# STM32F7.net
KiCad netlist of a schematic drawn in Altium Designer
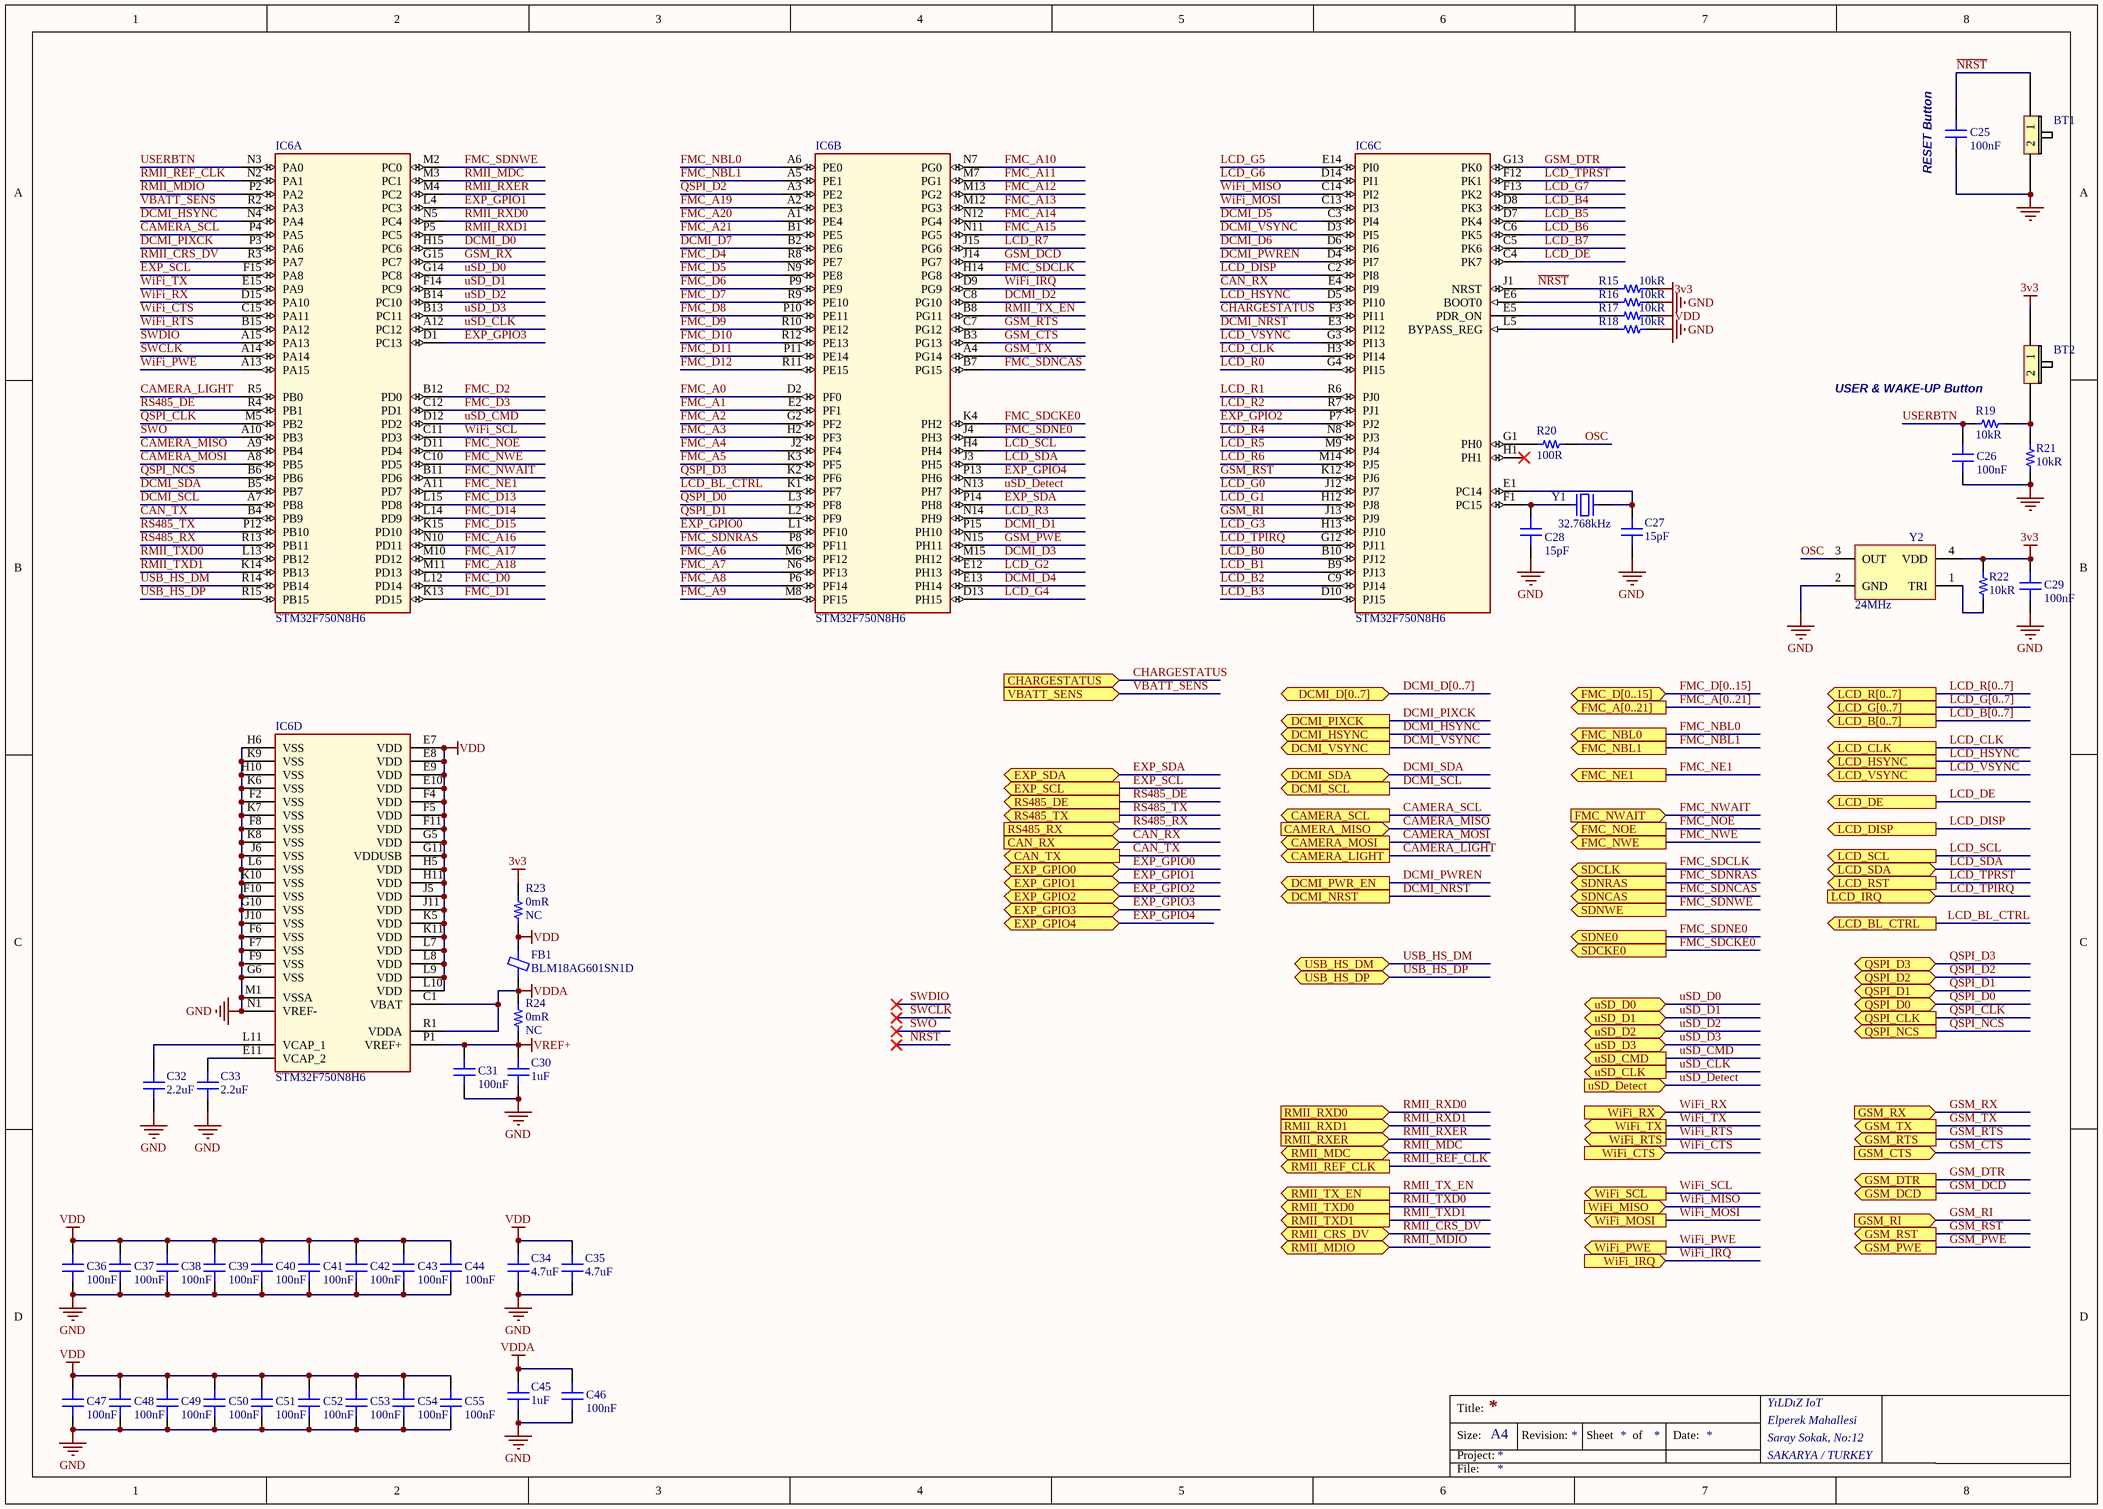
[diagram p0: STM32F7.SchDoc]

(export (version "E")
  (design (tool "Eeschema 10.0.6"))
  (components
    (comp (ref "BT1")
      (value "EVQP7J01P")
      (footprint "TactileButton")
      (description "Button, 2 pin")
      (fields (field (name "MANUFACTURER") "Panasonic"))
      (libsource (lib "Muhammet_All_In_One") (part "Button"))
    )
    (comp (ref "BT2")
      (value "EVQP7J01P")
      (footprint "TactileButton")
      (description "Button, 2 pin")
      (fields (field (name "MANUFACTURER") "Panasonic"))
      (libsource (lib "Muhammet_All_In_One") (part "Button"))
    )
    (comp (ref "C25")
      (value "100nF")
      (footprint "CAP 0603/1608")
      (description "Ceramic, SMT Capacitor")
      (fields
        (field (name "MANUFACTURER") "Samsung")
        (field (name "MANUFACTURER PART NUMBER") "CL10B104JB8NNNC")
      )
      (libsource (lib "yildizIoT Library") (part "Capacitor - Ceramic"))
    )
    (comp (ref "C26")
      (value "100nF")
      (footprint "CAP 0603/1608")
      (description "Ceramic, SMT Capacitor")
      (fields
        (field (name "MANUFACTURER") "Samsung")
        (field (name "MANUFACTURER PART NUMBER") "CL10B104JB8NNNC")
      )
      (libsource (lib "yildizIoT Library") (part "Capacitor - Ceramic"))
    )
    (comp (ref "C27")
      (value "15pF")
      (footprint "CAP 0603/1608")
      (description "Ceramic, SMT Capacitor")
      (fields
        (field (name "MANUFACTURER") "Walsin Technologies")
        (field (name "MANUFACTURER PART NUMBER") "0603N150J500CT")
      )
      (libsource (lib "yildizIoT Library") (part "Capacitor - Ceramic"))
    )
    (comp (ref "C28")
      (value "15pF")
      (footprint "CAP 0603/1608")
      (description "Ceramic, SMT Capacitor")
      (fields
        (field (name "MANUFACTURER") "Walsin Technologies")
        (field (name "MANUFACTURER PART NUMBER") "0603N150J500CT")
      )
      (libsource (lib "yildizIoT Library") (part "Capacitor - Ceramic"))
    )
    (comp (ref "C29")
      (value "100nF")
      (footprint "CAP 0603/1608")
      (description "Ceramic, SMT Capacitor")
      (fields
        (field (name "MANUFACTURER") "Samsung")
        (field (name "MANUFACTURER PART NUMBER") "CL10B104JB8NNNC")
      )
      (libsource (lib "yildizIoT Library") (part "Capacitor - Ceramic"))
    )
    (comp (ref "C30")
      (value "1uF")
      (footprint "CAP 0603/1608")
      (description "Ceramic, SMT Capacitor")
      (fields
        (field (name "MANUFACTURER") "Samsung")
        (field (name "MANUFACTURER PART NUMBER") "CL10A105KP8NNNC")
      )
      (libsource (lib "yildizIoT Library") (part "Capacitor - Ceramic"))
    )
    (comp (ref "C31")
      (value "100nF")
      (footprint "CAP 0603/1608")
      (description "Ceramic, SMT Capacitor")
      (fields
        (field (name "MANUFACTURER") "Samsung")
        (field (name "MANUFACTURER PART NUMBER") "CL10B104JB8NNNC")
      )
      (libsource (lib "yildizIoT Library") (part "Capacitor - Ceramic"))
    )
    (comp (ref "C32")
      (value "2.2uF")
      (footprint "CAP 0603/1608")
      (description "Ceramic, SMT Capacitor")
      (fields
        (field (name "MANUFACTURER") "Samsung")
        (field (name "MANUFACTURER PART NUMBER") "CL10A225KQ8NNNC")
      )
      (libsource (lib "yildizIoT Library") (part "Capacitor - Ceramic"))
    )
    (comp (ref "C33")
      (value "2.2uF")
      (footprint "CAP 0603/1608")
      (description "Ceramic, SMT Capacitor")
      (fields
        (field (name "MANUFACTURER") "Samsung")
        (field (name "MANUFACTURER PART NUMBER") "CL10A225KQ8NNNC")
      )
      (libsource (lib "yildizIoT Library") (part "Capacitor - Ceramic"))
    )
    (comp (ref "C34")
      (value "4.7uF")
      (footprint "CAP 0603/1608")
      (description "Ceramic, SMT Capacitor")
      (fields
        (field (name "MANUFACTURER") "Samsung")
        (field (name "MANUFACTURER PART NUMBER") "CL10A475MQ8NNNC")
      )
      (libsource (lib "yildizIoT Library") (part "Capacitor - Ceramic"))
    )
    (comp (ref "C35")
      (value "4.7uF")
      (footprint "CAP 0603/1608")
      (description "Ceramic, SMT Capacitor")
      (fields
        (field (name "MANUFACTURER") "Samsung")
        (field (name "MANUFACTURER PART NUMBER") "CL10A475MQ8NNNC")
      )
      (libsource (lib "yildizIoT Library") (part "Capacitor - Ceramic"))
    )
    (comp (ref "C36")
      (value "100nF")
      (footprint "CAP 0603/1608")
      (description "Ceramic, SMT Capacitor")
      (fields
        (field (name "MANUFACTURER") "Samsung")
        (field (name "MANUFACTURER PART NUMBER") "CL10B104JB8NNNC")
      )
      (libsource (lib "yildizIoT Library") (part "Capacitor - Ceramic"))
    )
    (comp (ref "C37")
      (value "100nF")
      (footprint "CAP 0603/1608")
      (description "Ceramic, SMT Capacitor")
      (fields
        (field (name "MANUFACTURER") "Samsung")
        (field (name "MANUFACTURER PART NUMBER") "CL10B104JB8NNNC")
      )
      (libsource (lib "yildizIoT Library") (part "Capacitor - Ceramic"))
    )
    (comp (ref "C38")
      (value "100nF")
      (footprint "CAP 0603/1608")
      (description "Ceramic, SMT Capacitor")
      (fields
        (field (name "MANUFACTURER") "Samsung")
        (field (name "MANUFACTURER PART NUMBER") "CL10B104JB8NNNC")
      )
      (libsource (lib "yildizIoT Library") (part "Capacitor - Ceramic"))
    )
    (comp (ref "C39")
      (value "100nF")
      (footprint "CAP 0603/1608")
      (description "Ceramic, SMT Capacitor")
      (fields
        (field (name "MANUFACTURER") "Samsung")
        (field (name "MANUFACTURER PART NUMBER") "CL10B104JB8NNNC")
      )
      (libsource (lib "yildizIoT Library") (part "Capacitor - Ceramic"))
    )
    (comp (ref "C40")
      (value "100nF")
      (footprint "CAP 0603/1608")
      (description "Ceramic, SMT Capacitor")
      (fields
        (field (name "MANUFACTURER") "Samsung")
        (field (name "MANUFACTURER PART NUMBER") "CL10B104JB8NNNC")
      )
      (libsource (lib "yildizIoT Library") (part "Capacitor - Ceramic"))
    )
    (comp (ref "C41")
      (value "100nF")
      (footprint "CAP 0603/1608")
      (description "Ceramic, SMT Capacitor")
      (fields
        (field (name "MANUFACTURER") "Samsung")
        (field (name "MANUFACTURER PART NUMBER") "CL10B104JB8NNNC")
      )
      (libsource (lib "yildizIoT Library") (part "Capacitor - Ceramic"))
    )
    (comp (ref "C42")
      (value "100nF")
      (footprint "CAP 0603/1608")
      (description "Ceramic, SMT Capacitor")
      (fields
        (field (name "MANUFACTURER") "Samsung")
        (field (name "MANUFACTURER PART NUMBER") "CL10B104JB8NNNC")
      )
      (libsource (lib "yildizIoT Library") (part "Capacitor - Ceramic"))
    )
    (comp (ref "C43")
      (value "100nF")
      (footprint "CAP 0603/1608")
      (description "Ceramic, SMT Capacitor")
      (fields
        (field (name "MANUFACTURER") "Samsung")
        (field (name "MANUFACTURER PART NUMBER") "CL10B104JB8NNNC")
      )
      (libsource (lib "yildizIoT Library") (part "Capacitor - Ceramic"))
    )
    (comp (ref "C44")
      (value "100nF")
      (footprint "CAP 0603/1608")
      (description "Ceramic, SMT Capacitor")
      (fields
        (field (name "MANUFACTURER") "Samsung")
        (field (name "MANUFACTURER PART NUMBER") "CL10B104JB8NNNC")
      )
      (libsource (lib "yildizIoT Library") (part "Capacitor - Ceramic"))
    )
    (comp (ref "C45")
      (value "1uF")
      (footprint "CAP 0603/1608")
      (description "Ceramic, SMT Capacitor")
      (fields
        (field (name "MANUFACTURER") "Samsung")
        (field (name "MANUFACTURER PART NUMBER") "CL10A105KP8NNNC")
      )
      (libsource (lib "yildizIoT Library") (part "Capacitor - Ceramic"))
    )
    (comp (ref "C46")
      (value "100nF")
      (footprint "CAP 0603/1608")
      (description "Ceramic, SMT Capacitor")
      (fields
        (field (name "MANUFACTURER") "Samsung")
        (field (name "MANUFACTURER PART NUMBER") "CL10B104JB8NNNC")
      )
      (libsource (lib "yildizIoT Library") (part "Capacitor - Ceramic"))
    )
    (comp (ref "C47")
      (value "100nF")
      (footprint "CAP 0603/1608")
      (description "Ceramic, SMT Capacitor")
      (fields
        (field (name "MANUFACTURER") "Samsung")
        (field (name "MANUFACTURER PART NUMBER") "CL10B104JB8NNNC")
      )
      (libsource (lib "yildizIoT Library") (part "Capacitor - Ceramic"))
    )
    (comp (ref "C48")
      (value "100nF")
      (footprint "CAP 0603/1608")
      (description "Ceramic, SMT Capacitor")
      (fields
        (field (name "MANUFACTURER") "Samsung")
        (field (name "MANUFACTURER PART NUMBER") "CL10B104JB8NNNC")
      )
      (libsource (lib "yildizIoT Library") (part "Capacitor - Ceramic"))
    )
    (comp (ref "C49")
      (value "100nF")
      (footprint "CAP 0603/1608")
      (description "Ceramic, SMT Capacitor")
      (fields
        (field (name "MANUFACTURER") "Samsung")
        (field (name "MANUFACTURER PART NUMBER") "CL10B104JB8NNNC")
      )
      (libsource (lib "yildizIoT Library") (part "Capacitor - Ceramic"))
    )
    (comp (ref "C50")
      (value "100nF")
      (footprint "CAP 0603/1608")
      (description "Ceramic, SMT Capacitor")
      (fields
        (field (name "MANUFACTURER") "Samsung")
        (field (name "MANUFACTURER PART NUMBER") "CL10B104JB8NNNC")
      )
      (libsource (lib "yildizIoT Library") (part "Capacitor - Ceramic"))
    )
    (comp (ref "C51")
      (value "100nF")
      (footprint "CAP 0603/1608")
      (description "Ceramic, SMT Capacitor")
      (fields
        (field (name "MANUFACTURER") "Samsung")
        (field (name "MANUFACTURER PART NUMBER") "CL10B104JB8NNNC")
      )
      (libsource (lib "yildizIoT Library") (part "Capacitor - Ceramic"))
    )
    (comp (ref "C52")
      (value "100nF")
      (footprint "CAP 0603/1608")
      (description "Ceramic, SMT Capacitor")
      (fields
        (field (name "MANUFACTURER") "Samsung")
        (field (name "MANUFACTURER PART NUMBER") "CL10B104JB8NNNC")
      )
      (libsource (lib "yildizIoT Library") (part "Capacitor - Ceramic"))
    )
    (comp (ref "C53")
      (value "100nF")
      (footprint "CAP 0603/1608")
      (description "Ceramic, SMT Capacitor")
      (fields
        (field (name "MANUFACTURER") "Samsung")
        (field (name "MANUFACTURER PART NUMBER") "CL10B104JB8NNNC")
      )
      (libsource (lib "yildizIoT Library") (part "Capacitor - Ceramic"))
    )
    (comp (ref "C54")
      (value "100nF")
      (footprint "CAP 0603/1608")
      (description "Ceramic, SMT Capacitor")
      (fields
        (field (name "MANUFACTURER") "Samsung")
        (field (name "MANUFACTURER PART NUMBER") "CL10B104JB8NNNC")
      )
      (libsource (lib "yildizIoT Library") (part "Capacitor - Ceramic"))
    )
    (comp (ref "C55")
      (value "100nF")
      (footprint "CAP 0603/1608")
      (description "Ceramic, SMT Capacitor")
      (fields
        (field (name "MANUFACTURER") "Samsung")
        (field (name "MANUFACTURER PART NUMBER") "CL10B104JB8NNNC")
      )
      (libsource (lib "yildizIoT Library") (part "Capacitor - Ceramic"))
    )
    (comp (ref "FB1")
      (value "BLM18AG601SN1D")
      (footprint "FER 0603/1608")
      (description "SMT Ferrite Chip")
      (fields (field (name "MANUFACTURER") "Murata") (field (name "TOLERANCE") "25%"))
      (libsource (lib "yildizIoT Library") (part "Ferrite Chip"))
    )
    (comp (ref "IC6")
      (value "STM32F750N8H6")
      (footprint "ST TFBGA-216 13x13 0.8mm")
      (fields (field (name "MANUFACTURER") "STMicroelectronics"))
      (libsource (lib "") (part "ST STM32F75XNXH 216 PIN_2"))
    )
    (comp (ref "R15")
      (value "10kR")
      (footprint "RES 0603/1608")
      (description "Ceramic, SMT Capacitor")
      (fields
        (field (name "MANUFACTURER") "Stackpole Electronics")
        (field (name "MANUFACTURER PART NUMBER") "RNCP0603FTD10K0")
      )
      (libsource (lib "yildizIoT Library") (part "Resistor_Chip"))
    )
    (comp (ref "R16")
      (value "10kR")
      (footprint "RES 0603/1608")
      (description "Ceramic, SMT Capacitor")
      (fields
        (field (name "MANUFACTURER") "Stackpole Electronics")
        (field (name "MANUFACTURER PART NUMBER") "RNCP0603FTD10K0")
      )
      (libsource (lib "yildizIoT Library") (part "Resistor_Chip"))
    )
    (comp (ref "R17")
      (value "10kR")
      (footprint "RES 0603/1608")
      (description "Ceramic, SMT Capacitor")
      (fields
        (field (name "MANUFACTURER") "Stackpole Electronics")
        (field (name "MANUFACTURER PART NUMBER") "RNCP0603FTD10K0")
      )
      (libsource (lib "yildizIoT Library") (part "Resistor_Chip"))
    )
    (comp (ref "R18")
      (value "10kR")
      (footprint "RES 0603/1608")
      (description "Ceramic, SMT Capacitor")
      (fields
        (field (name "MANUFACTURER") "Stackpole Electronics")
        (field (name "MANUFACTURER PART NUMBER") "RNCP0603FTD10K0")
      )
      (libsource (lib "yildizIoT Library") (part "Resistor_Chip"))
    )
    (comp (ref "R19")
      (value "10kR")
      (footprint "RES 0603/1608")
      (description "Ceramic, SMT Capacitor")
      (fields
        (field (name "MANUFACTURER") "Stackpole Electronics")
        (field (name "MANUFACTURER PART NUMBER") "RNCP0603FTD10K0")
      )
      (libsource (lib "yildizIoT Library") (part "Resistor_Chip"))
    )
    (comp (ref "R20")
      (value "100R")
      (footprint "RES 0603/1608")
      (description "Ceramic, SMT Capacitor")
      (fields
        (field (name "MANUFACTURER") "Stackpole Electronics")
        (field (name "MANUFACTURER PART NUMBER") "RMCF0603FT100R")
      )
      (libsource (lib "yildizIoT Library") (part "Resistor_Chip"))
    )
    (comp (ref "R21")
      (value "10kR")
      (footprint "RES 0603/1608")
      (description "Ceramic, SMT Capacitor")
      (fields
        (field (name "MANUFACTURER") "Stackpole Electronics")
        (field (name "MANUFACTURER PART NUMBER") "RNCP0603FTD10K0")
      )
      (libsource (lib "yildizIoT Library") (part "Resistor_Chip"))
    )
    (comp (ref "R22")
      (value "10kR")
      (footprint "RES 0603/1608")
      (description "Ceramic, SMT Capacitor")
      (fields
        (field (name "MANUFACTURER") "Stackpole Electronics")
        (field (name "MANUFACTURER PART NUMBER") "RNCP0603FTD10K0")
      )
      (libsource (lib "yildizIoT Library") (part "Resistor_Chip"))
    )
    (comp (ref "R23")
      (value "0mR")
      (footprint "RES 0603/1608")
      (description "Ceramic, SMT Capacitor")
      (fields
        (field (name "MANUFACTURER") "Stackpole Electronics")
        (field (name "MANUFACTURER PART NUMBER") "RMCF0603ZT0R00")
        (field (name "NC") "NC")
      )
      (libsource (lib "yildizIoT Library") (part "Resistor_Chip"))
    )
    (comp (ref "R24")
      (value "0mR")
      (footprint "RES 0603/1608")
      (description "Ceramic, SMT Capacitor")
      (fields
        (field (name "MANUFACTURER") "Stackpole Electronics")
        (field (name "MANUFACTURER PART NUMBER") "RMCF0603ZT0R00")
        (field (name "NC") "NC")
      )
      (libsource (lib "yildizIoT Library") (part "Resistor_Chip"))
    )
    (comp (ref "Y1")
      (value "32.768kHz")
      (footprint "ABRACON ABS06")
      (description "CRYSTAL 32.7680KHZ 12.5PF SMD")
      (fields
        (field (name "MANUFACTURER PART NUMBER") "ABS06-32.768KHZ-1-T")
        (field (name "MANUFACTURER") "Abracon LLC")
      )
      (libsource (lib "Celestial Library Database") (part "Abracon Crystal ABS06"))
    )
    (comp (ref "Y2")
      (value "24MHz")
      (footprint "Abracon ASTX-11")
      (description "OSC XO 1.544MHZ CMOS SMD")
      (fields
        (field (name "MANUFACTURER") "ECS Inc.")
        (field (name "MANUFACTURER PART NUMBER") "ECS-3225MV-240-CN-TR")
      )
      (libsource (lib "Celestial Library Database") (part "Abracon XO ASD"))
    )
  )
  (nets
    (net (code "1") (name "/CAMERA_LIGHT") (class "Default")
      (node (ref "IC6") (pin "R5") (pinfunction "PB0_R5") (pintype "bidirectional"))
    )
    (net (code "2") (name "/CAMERA_MISO") (class "Default")
      (node (ref "IC6") (pin "A9") (pinfunction "PB4_A9") (pintype "bidirectional"))
    )
    (net (code "3") (name "/CAMERA_MOSI") (class "Default")
      (node (ref "IC6") (pin "A8") (pinfunction "PB5_A8") (pintype "bidirectional"))
    )
    (net (code "4") (name "/CAMERA_SCL") (class "Default")
      (node (ref "IC6") (pin "P4") (pinfunction "PA5_P4") (pintype "bidirectional"))
    )
    (net (code "5") (name "/CAN_RX") (class "Default")
      (node (ref "IC6") (pin "E4") (pinfunction "PI9_E4") (pintype "bidirectional"))
    )
    (net (code "6") (name "/CAN_TX") (class "Default")
      (node (ref "IC6") (pin "B4") (pinfunction "PB9_B4") (pintype "bidirectional"))
    )
    (net (code "7") (name "/CHARGESTATUS") (class "Default")
      (node (ref "IC6") (pin "F3") (pinfunction "PI11_F3") (pintype "bidirectional"))
    )
    (net (code "8") (name "/DCMI_D0") (class "Default")
      (node (ref "IC6") (pin "H15") (pinfunction "PC6_H15") (pintype "bidirectional"))
    )
    (net (code "9") (name "/DCMI_D1") (class "Default")
      (node (ref "IC6") (pin "P15") (pinfunction "PH10_P15") (pintype "bidirectional"))
    )
    (net (code "10") (name "/DCMI_D2") (class "Default")
      (node (ref "IC6") (pin "C8") (pinfunction "PG10_C8") (pintype "bidirectional"))
    )
    (net (code "11") (name "/DCMI_D3") (class "Default")
      (node (ref "IC6") (pin "M15") (pinfunction "PH12_M15") (pintype "bidirectional"))
    )
    (net (code "12") (name "/DCMI_D4") (class "Default")
      (node (ref "IC6") (pin "E13") (pinfunction "PH14_E13") (pintype "bidirectional"))
    )
    (net (code "13") (name "/DCMI_D5") (class "Default")
      (node (ref "IC6") (pin "C3") (pinfunction "PI4_C3") (pintype "bidirectional"))
    )
    (net (code "14") (name "/DCMI_D6") (class "Default")
      (node (ref "IC6") (pin "D6") (pinfunction "PI6_D6") (pintype "bidirectional"))
    )
    (net (code "15") (name "/DCMI_D7") (class "Default")
      (node (ref "IC6") (pin "B2") (pinfunction "PE6_B2") (pintype "bidirectional"))
    )
    (net (code "17") (name "/DCMI_HSYNC") (class "Default")
      (node (ref "IC6") (pin "N4") (pinfunction "PA4_N4") (pintype "bidirectional"))
    )
    (net (code "18") (name "/DCMI_NRST") (class "Default")
      (node (ref "IC6") (pin "E3") (pinfunction "PI12_E3") (pintype "bidirectional"))
    )
    (net (code "19") (name "/DCMI_PIXCK") (class "Default")
      (node (ref "IC6") (pin "P3") (pinfunction "PA6_P3") (pintype "bidirectional"))
    )
    (net (code "20") (name "/DCMI_PWREN") (class "Default")
      (node (ref "IC6") (pin "D4") (pinfunction "PI7_D4") (pintype "bidirectional"))
    )
    (net (code "21") (name "/DCMI_SCL") (class "Default")
      (node (ref "IC6") (pin "A7") (pinfunction "PB8_A7") (pintype "bidirectional"))
    )
    (net (code "22") (name "/DCMI_SDA") (class "Default")
      (node (ref "IC6") (pin "B5") (pinfunction "PB7_B5") (pintype "bidirectional"))
    )
    (net (code "23") (name "/DCMI_VSYNC") (class "Default")
      (node (ref "IC6") (pin "D3") (pinfunction "PI5_D3") (pintype "bidirectional"))
    )
    (net (code "24") (name "/EXP_GPIO0") (class "Default")
      (node (ref "IC6") (pin "L1") (pinfunction "PF10_L1") (pintype "bidirectional"))
    )
    (net (code "25") (name "/EXP_GPIO1") (class "Default")
      (node (ref "IC6") (pin "L4") (pinfunction "PC3_L4") (pintype "bidirectional"))
    )
    (net (code "26") (name "/EXP_GPIO2") (class "Default")
      (node (ref "IC6") (pin "P7") (pinfunction "PJ2_P7") (pintype "bidirectional"))
    )
    (net (code "27") (name "/EXP_GPIO3") (class "Default")
      (node (ref "IC6") (pin "D1") (pinfunction "PC13_D1") (pintype "bidirectional"))
    )
    (net (code "28") (name "/EXP_GPIO4") (class "Default")
      (node (ref "IC6") (pin "P13") (pinfunction "PH6_P13") (pintype "bidirectional"))
    )
    (net (code "29") (name "/EXP_SCL") (class "Default")
      (node (ref "IC6") (pin "F15") (pinfunction "PA8_F15") (pintype "bidirectional"))
    )
    (net (code "30") (name "/EXP_SDA") (class "Default")
      (node (ref "IC6") (pin "P14") (pinfunction "PH8_P14") (pintype "bidirectional"))
    )
    (net (code "31") (name "/FMC_A0") (class "Default")
      (node (ref "IC6") (pin "D2") (pinfunction "PF0_D2") (pintype "bidirectional"))
    )
    (net (code "32") (name "/FMC_A1") (class "Default")
      (node (ref "IC6") (pin "E2") (pinfunction "PF1_E2") (pintype "bidirectional"))
    )
    (net (code "33") (name "/FMC_A2") (class "Default")
      (node (ref "IC6") (pin "G2") (pinfunction "PF2_G2") (pintype "bidirectional"))
    )
    (net (code "34") (name "/FMC_A3") (class "Default")
      (node (ref "IC6") (pin "H2") (pinfunction "PF3_H2") (pintype "bidirectional"))
    )
    (net (code "35") (name "/FMC_A4") (class "Default")
      (node (ref "IC6") (pin "J2") (pinfunction "PF4_J2") (pintype "bidirectional"))
    )
    (net (code "36") (name "/FMC_A5") (class "Default")
      (node (ref "IC6") (pin "K3") (pinfunction "PF5_K3") (pintype "bidirectional"))
    )
    (net (code "37") (name "/FMC_A6") (class "Default")
      (node (ref "IC6") (pin "M6") (pinfunction "PF12_M6") (pintype "bidirectional"))
    )
    (net (code "38") (name "/FMC_A7") (class "Default")
      (node (ref "IC6") (pin "N6") (pinfunction "PF13_N6") (pintype "bidirectional"))
    )
    (net (code "39") (name "/FMC_A8") (class "Default")
      (node (ref "IC6") (pin "P6") (pinfunction "PF14_P6") (pintype "bidirectional"))
    )
    (net (code "40") (name "/FMC_A9") (class "Default")
      (node (ref "IC6") (pin "M8") (pinfunction "PF15_M8") (pintype "bidirectional"))
    )
    (net (code "41") (name "/FMC_A10") (class "Default")
      (node (ref "IC6") (pin "N7") (pinfunction "PG0_N7") (pintype "bidirectional"))
    )
    (net (code "42") (name "/FMC_A11") (class "Default")
      (node (ref "IC6") (pin "M7") (pinfunction "PG1_M7") (pintype "bidirectional"))
    )
    (net (code "43") (name "/FMC_A12") (class "Default")
      (node (ref "IC6") (pin "M13") (pinfunction "PG2_M13") (pintype "bidirectional"))
    )
    (net (code "44") (name "/FMC_A13") (class "Default")
      (node (ref "IC6") (pin "M12") (pinfunction "PG3_M12") (pintype "bidirectional"))
    )
    (net (code "45") (name "/FMC_A14") (class "Default")
      (node (ref "IC6") (pin "N12") (pinfunction "PG4_N12") (pintype "bidirectional"))
    )
    (net (code "46") (name "/FMC_A15") (class "Default")
      (node (ref "IC6") (pin "N11") (pinfunction "PG5_N11") (pintype "bidirectional"))
    )
    (net (code "47") (name "/FMC_A16") (class "Default")
      (node (ref "IC6") (pin "N10") (pinfunction "PD11_N10") (pintype "bidirectional"))
    )
    (net (code "48") (name "/FMC_A17") (class "Default")
      (node (ref "IC6") (pin "M10") (pinfunction "PD12_M10") (pintype "bidirectional"))
    )
    (net (code "49") (name "/FMC_A18") (class "Default")
      (node (ref "IC6") (pin "M11") (pinfunction "PD13_M11") (pintype "bidirectional"))
    )
    (net (code "50") (name "/FMC_A19") (class "Default")
      (node (ref "IC6") (pin "A2") (pinfunction "PE3_A2") (pintype "bidirectional"))
    )
    (net (code "51") (name "/FMC_A20") (class "Default")
      (node (ref "IC6") (pin "A1") (pinfunction "PE4_A1") (pintype "bidirectional"))
    )
    (net (code "52") (name "/FMC_A21") (class "Default")
      (node (ref "IC6") (pin "B1") (pinfunction "PE5_B1") (pintype "bidirectional"))
    )
    (net (code "54") (name "/FMC_D0") (class "Default")
      (node (ref "IC6") (pin "L12") (pinfunction "PD14_L12") (pintype "bidirectional"))
    )
    (net (code "55") (name "/FMC_D1") (class "Default")
      (node (ref "IC6") (pin "K13") (pinfunction "PD15_K13") (pintype "bidirectional"))
    )
    (net (code "56") (name "/FMC_D2") (class "Default")
      (node (ref "IC6") (pin "B12") (pinfunction "PD0_B12") (pintype "bidirectional"))
    )
    (net (code "57") (name "/FMC_D3") (class "Default")
      (node (ref "IC6") (pin "C12") (pinfunction "PD1_C12") (pintype "bidirectional"))
    )
    (net (code "58") (name "/FMC_D4") (class "Default")
      (node (ref "IC6") (pin "R8") (pinfunction "PE7_R8") (pintype "bidirectional"))
    )
    (net (code "59") (name "/FMC_D5") (class "Default")
      (node (ref "IC6") (pin "N9") (pinfunction "PE8_N9") (pintype "bidirectional"))
    )
    (net (code "60") (name "/FMC_D6") (class "Default")
      (node (ref "IC6") (pin "P9") (pinfunction "PE9_P9") (pintype "bidirectional"))
    )
    (net (code "61") (name "/FMC_D7") (class "Default")
      (node (ref "IC6") (pin "R9") (pinfunction "PE10_R9") (pintype "bidirectional"))
    )
    (net (code "62") (name "/FMC_D8") (class "Default")
      (node (ref "IC6") (pin "P10") (pinfunction "PE11_P10") (pintype "bidirectional"))
    )
    (net (code "63") (name "/FMC_D9") (class "Default")
      (node (ref "IC6") (pin "R10") (pinfunction "PE12_R10") (pintype "bidirectional"))
    )
    (net (code "64") (name "/FMC_D10") (class "Default")
      (node (ref "IC6") (pin "R12") (pinfunction "PE13_R12") (pintype "bidirectional"))
    )
    (net (code "65") (name "/FMC_D11") (class "Default")
      (node (ref "IC6") (pin "P11") (pinfunction "PE14_P11") (pintype "bidirectional"))
    )
    (net (code "66") (name "/FMC_D12") (class "Default")
      (node (ref "IC6") (pin "R11") (pinfunction "PE15_R11") (pintype "bidirectional"))
    )
    (net (code "67") (name "/FMC_D13") (class "Default")
      (node (ref "IC6") (pin "L15") (pinfunction "PD8_L15") (pintype "bidirectional"))
    )
    (net (code "68") (name "/FMC_D14") (class "Default")
      (node (ref "IC6") (pin "L14") (pinfunction "PD9_L14") (pintype "bidirectional"))
    )
    (net (code "69") (name "/FMC_D15") (class "Default")
      (node (ref "IC6") (pin "K15") (pinfunction "PD10_K15") (pintype "bidirectional"))
    )
    (net (code "71") (name "/FMC_NBL0") (class "Default")
      (node (ref "IC6") (pin "A6") (pinfunction "PE0_A6") (pintype "bidirectional"))
    )
    (net (code "72") (name "/FMC_NBL1") (class "Default")
      (node (ref "IC6") (pin "A5") (pinfunction "PE1_A5") (pintype "bidirectional"))
    )
    (net (code "73") (name "/FMC_NE1") (class "Default")
      (node (ref "IC6") (pin "A11") (pinfunction "PD7_A11") (pintype "bidirectional"))
    )
    (net (code "74") (name "/FMC_NOE") (class "Default")
      (node (ref "IC6") (pin "D11") (pinfunction "PD4_D11") (pintype "bidirectional"))
    )
    (net (code "75") (name "/FMC_NWAIT") (class "Default")
      (node (ref "IC6") (pin "B11") (pinfunction "PD6_B11") (pintype "bidirectional"))
    )
    (net (code "76") (name "/FMC_NWE") (class "Default")
      (node (ref "IC6") (pin "C10") (pinfunction "PD5_C10") (pintype "bidirectional"))
    )
    (net (code "77") (name "/FMC_SDCKE0") (class "Default")
      (node (ref "IC6") (pin "K4") (pinfunction "PH2_K4") (pintype "bidirectional"))
    )
    (net (code "78") (name "/FMC_SDCLK") (class "Default")
      (node (ref "IC6") (pin "H14") (pinfunction "PG8_H14") (pintype "bidirectional"))
    )
    (net (code "79") (name "/FMC_SDNCAS") (class "Default")
      (node (ref "IC6") (pin "B7") (pinfunction "PG15_B7") (pintype "bidirectional"))
    )
    (net (code "80") (name "/FMC_SDNE0") (class "Default")
      (node (ref "IC6") (pin "J4") (pinfunction "PH3_J4") (pintype "bidirectional"))
    )
    (net (code "81") (name "/FMC_SDNRAS") (class "Default")
      (node (ref "IC6") (pin "P8") (pinfunction "PF11_P8") (pintype "bidirectional"))
    )
    (net (code "82") (name "/FMC_SDNWE") (class "Default")
      (node (ref "IC6") (pin "M2") (pinfunction "PC0_M2") (pintype "bidirectional"))
    )
    (net (code "83") (name "/GSM_CTS") (class "Default")
      (node (ref "IC6") (pin "B3") (pinfunction "PG13_B3") (pintype "bidirectional"))
    )
    (net (code "84") (name "/GSM_DCD") (class "Default")
      (node (ref "IC6") (pin "J14") (pinfunction "PG7_J14") (pintype "bidirectional"))
    )
    (net (code "85") (name "/GSM_DTR") (class "Default")
      (node (ref "IC6") (pin "G13") (pinfunction "PK0_G13") (pintype "bidirectional"))
    )
    (net (code "86") (name "/GSM_PWE") (class "Default")
      (node (ref "IC6") (pin "N15") (pinfunction "PH11_N15") (pintype "bidirectional"))
    )
    (net (code "87") (name "/GSM_RI") (class "Default")
      (node (ref "IC6") (pin "J13") (pinfunction "PJ9_J13") (pintype "bidirectional"))
    )
    (net (code "88") (name "/GSM_RST") (class "Default")
      (node (ref "IC6") (pin "K12") (pinfunction "PJ6_K12") (pintype "bidirectional"))
    )
    (net (code "89") (name "/GSM_RTS") (class "Default")
      (node (ref "IC6") (pin "C7") (pinfunction "PG12_C7") (pintype "bidirectional"))
    )
    (net (code "90") (name "/GSM_RX") (class "Default")
      (node (ref "IC6") (pin "G15") (pinfunction "PC7_G15") (pintype "bidirectional"))
    )
    (net (code "91") (name "/GSM_TX") (class "Default")
      (node (ref "IC6") (pin "A4") (pinfunction "PG14_A4") (pintype "bidirectional"))
    )
    (net (code "92") (name "/LCD_B0") (class "Default")
      (node (ref "IC6") (pin "B10") (pinfunction "PJ12_B10") (pintype "bidirectional"))
    )
    (net (code "93") (name "/LCD_B1") (class "Default")
      (node (ref "IC6") (pin "B9") (pinfunction "PJ13_B9") (pintype "bidirectional"))
    )
    (net (code "94") (name "/LCD_B2") (class "Default")
      (node (ref "IC6") (pin "C9") (pinfunction "PJ14_C9") (pintype "bidirectional"))
    )
    (net (code "95") (name "/LCD_B3") (class "Default")
      (node (ref "IC6") (pin "D10") (pinfunction "PJ15_D10") (pintype "bidirectional"))
    )
    (net (code "96") (name "/LCD_B4") (class "Default")
      (node (ref "IC6") (pin "D8") (pinfunction "PK3_D8") (pintype "bidirectional"))
    )
    (net (code "97") (name "/LCD_B5") (class "Default")
      (node (ref "IC6") (pin "D7") (pinfunction "PK4_D7") (pintype "bidirectional"))
    )
    (net (code "98") (name "/LCD_B6") (class "Default")
      (node (ref "IC6") (pin "C6") (pinfunction "PK5_C6") (pintype "bidirectional"))
    )
    (net (code "99") (name "/LCD_B7") (class "Default")
      (node (ref "IC6") (pin "C5") (pinfunction "PK6_C5") (pintype "bidirectional"))
    )
    (net (code "100") (name "/LCD_BL_CTRL") (class "Default")
      (node (ref "IC6") (pin "K1") (pinfunction "PF7_K1") (pintype "bidirectional"))
    )
    (net (code "102") (name "/LCD_CLK") (class "Default")
      (node (ref "IC6") (pin "H3") (pinfunction "PI14_H3") (pintype "bidirectional"))
    )
    (net (code "103") (name "/LCD_DE") (class "Default")
      (node (ref "IC6") (pin "C4") (pinfunction "PK7_C4") (pintype "bidirectional"))
    )
    (net (code "104") (name "/LCD_DISP") (class "Default")
      (node (ref "IC6") (pin "C2") (pinfunction "PI8_C2") (pintype "bidirectional"))
    )
    (net (code "105") (name "/LCD_G0") (class "Default")
      (node (ref "IC6") (pin "J12") (pinfunction "PJ7_J12") (pintype "bidirectional"))
    )
    (net (code "106") (name "/LCD_G1") (class "Default")
      (node (ref "IC6") (pin "H12") (pinfunction "PJ8_H12") (pintype "bidirectional"))
    )
    (net (code "107") (name "/LCD_G2") (class "Default")
      (node (ref "IC6") (pin "E12") (pinfunction "PH13_E12") (pintype "bidirectional"))
    )
    (net (code "108") (name "/LCD_G3") (class "Default")
      (node (ref "IC6") (pin "H13") (pinfunction "PJ10_H13") (pintype "bidirectional"))
    )
    (net (code "109") (name "/LCD_G4") (class "Default")
      (node (ref "IC6") (pin "D13") (pinfunction "PH15_D13") (pintype "bidirectional"))
    )
    (net (code "110") (name "/LCD_G5") (class "Default")
      (node (ref "IC6") (pin "E14") (pinfunction "PI0_E14") (pintype "bidirectional"))
    )
    (net (code "111") (name "/LCD_G6") (class "Default")
      (node (ref "IC6") (pin "D14") (pinfunction "PI1_D14") (pintype "bidirectional"))
    )
    (net (code "112") (name "/LCD_G7") (class "Default")
      (node (ref "IC6") (pin "F13") (pinfunction "PK2_F13") (pintype "bidirectional"))
    )
    (net (code "114") (name "/LCD_HSYNC") (class "Default")
      (node (ref "IC6") (pin "D5") (pinfunction "PI10_D5") (pintype "bidirectional"))
    )
    (net (code "115") (name "/LCD_R0") (class "Default")
      (node (ref "IC6") (pin "G4") (pinfunction "PI15_G4") (pintype "bidirectional"))
    )
    (net (code "116") (name "/LCD_R1") (class "Default")
      (node (ref "IC6") (pin "R6") (pinfunction "PJ0_R6") (pintype "bidirectional"))
    )
    (net (code "117") (name "/LCD_R2") (class "Default")
      (node (ref "IC6") (pin "R7") (pinfunction "PJ1_R7") (pintype "bidirectional"))
    )
    (net (code "118") (name "/LCD_R3") (class "Default")
      (node (ref "IC6") (pin "N14") (pinfunction "PH9_N14") (pintype "bidirectional"))
    )
    (net (code "119") (name "/LCD_R4") (class "Default")
      (node (ref "IC6") (pin "N8") (pinfunction "PJ3_N8") (pintype "bidirectional"))
    )
    (net (code "120") (name "/LCD_R5") (class "Default")
      (node (ref "IC6") (pin "M9") (pinfunction "PJ4_M9") (pintype "bidirectional"))
    )
    (net (code "121") (name "/LCD_R6") (class "Default")
      (node (ref "IC6") (pin "M14") (pinfunction "PJ5_M14") (pintype "bidirectional"))
    )
    (net (code "122") (name "/LCD_R7") (class "Default")
      (node (ref "IC6") (pin "J15") (pinfunction "PG6_J15") (pintype "bidirectional"))
    )
    (net (code "124") (name "/LCD_SCL") (class "Default")
      (node (ref "IC6") (pin "H4") (pinfunction "PH4_H4") (pintype "bidirectional"))
    )
    (net (code "125") (name "/LCD_SDA") (class "Default")
      (node (ref "IC6") (pin "J3") (pinfunction "PH5_J3") (pintype "bidirectional"))
    )
    (net (code "126") (name "/LCD_TPIRQ") (class "Default")
      (node (ref "IC6") (pin "G12") (pinfunction "PJ11_G12") (pintype "bidirectional"))
    )
    (net (code "127") (name "/LCD_TPRST") (class "Default")
      (node (ref "IC6") (pin "F12") (pinfunction "PK1_F12") (pintype "bidirectional"))
    )
    (net (code "128") (name "/LCD_VSYNC") (class "Default")
      (node (ref "IC6") (pin "G3") (pinfunction "PI13_G3") (pintype "bidirectional"))
    )
    (net (code "129") (name "/OSC") (class "Default")
      (node (ref "R20") (pin "2") (pinfunction "2_2") (pintype "passive"))
      (node (ref "Y2") (pin "3") (pinfunction "OUT_3") (pintype "passive"))
    )
    (net (code "130") (name "/QSPI_CLK") (class "Default")
      (node (ref "IC6") (pin "M5") (pinfunction "PB2_M5") (pintype "bidirectional"))
    )
    (net (code "131") (name "/QSPI_D0") (class "Default")
      (node (ref "IC6") (pin "L3") (pinfunction "PF8_L3") (pintype "bidirectional"))
    )
    (net (code "132") (name "/QSPI_D1") (class "Default")
      (node (ref "IC6") (pin "L2") (pinfunction "PF9_L2") (pintype "bidirectional"))
    )
    (net (code "133") (name "/QSPI_D2") (class "Default")
      (node (ref "IC6") (pin "A3") (pinfunction "PE2_A3") (pintype "bidirectional"))
    )
    (net (code "134") (name "/QSPI_D3") (class "Default")
      (node (ref "IC6") (pin "K2") (pinfunction "PF6_K2") (pintype "bidirectional"))
    )
    (net (code "135") (name "/QSPI_NCS") (class "Default")
      (node (ref "IC6") (pin "B6") (pinfunction "PB6_B6") (pintype "bidirectional"))
    )
    (net (code "136") (name "/RMII_CRS_DV") (class "Default")
      (node (ref "IC6") (pin "R3") (pinfunction "PA7_R3") (pintype "bidirectional"))
    )
    (net (code "137") (name "/RMII_MDC") (class "Default")
      (node (ref "IC6") (pin "M3") (pinfunction "PC1_M3") (pintype "bidirectional"))
    )
    (net (code "138") (name "/RMII_MDIO") (class "Default")
      (node (ref "IC6") (pin "P2") (pinfunction "PA2_P2") (pintype "bidirectional"))
    )
    (net (code "139") (name "/RMII_REF_CLK") (class "Default")
      (node (ref "IC6") (pin "N2") (pinfunction "PA1_N2") (pintype "bidirectional"))
    )
    (net (code "140") (name "/RMII_RXD0") (class "Default")
      (node (ref "IC6") (pin "N5") (pinfunction "PC4_N5") (pintype "bidirectional"))
    )
    (net (code "141") (name "/RMII_RXD1") (class "Default")
      (node (ref "IC6") (pin "P5") (pinfunction "PC5_P5") (pintype "bidirectional"))
    )
    (net (code "142") (name "/RMII_RXER") (class "Default")
      (node (ref "IC6") (pin "M4") (pinfunction "PC2_M4") (pintype "bidirectional"))
    )
    (net (code "143") (name "/RMII_TXD0") (class "Default")
      (node (ref "IC6") (pin "L13") (pinfunction "PB12_L13") (pintype "bidirectional"))
    )
    (net (code "144") (name "/RMII_TXD1") (class "Default")
      (node (ref "IC6") (pin "K14") (pinfunction "PB13_K14") (pintype "bidirectional"))
    )
    (net (code "145") (name "/RMII_TX_EN") (class "Default")
      (node (ref "IC6") (pin "B8") (pinfunction "PG11_B8") (pintype "bidirectional"))
    )
    (net (code "146") (name "/RS485_DE") (class "Default")
      (node (ref "IC6") (pin "R4") (pinfunction "PB1_R4") (pintype "bidirectional"))
    )
    (net (code "147") (name "/RS485_RX") (class "Default")
      (node (ref "IC6") (pin "R13") (pinfunction "PB11_R13") (pintype "bidirectional"))
    )
    (net (code "148") (name "/RS485_TX") (class "Default")
      (node (ref "IC6") (pin "P12") (pinfunction "PB10_P12") (pintype "bidirectional"))
    )
    (net (code "149") (name "/SWCLK") (class "Default")
      (node (ref "IC6") (pin "A14") (pinfunction "PA14_A14") (pintype "bidirectional"))
    )
    (net (code "150") (name "/SWDIO") (class "Default")
      (node (ref "IC6") (pin "A15") (pinfunction "PA13_A15") (pintype "bidirectional"))
    )
    (net (code "151") (name "/SWO") (class "Default")
      (node (ref "IC6") (pin "A10") (pinfunction "PB3_A10") (pintype "bidirectional"))
    )
    (net (code "152") (name "/USB_HS_DM") (class "Default")
      (node (ref "IC6") (pin "R14") (pinfunction "PB14_R14") (pintype "bidirectional"))
    )
    (net (code "153") (name "/USB_HS_DP") (class "Default")
      (node (ref "IC6") (pin "R15") (pinfunction "PB15_R15") (pintype "bidirectional"))
    )
    (net (code "154") (name "/USERBTN") (class "Default")
      (node (ref "C26") (pin "2") (pinfunction "2_2") (pintype "passive"))
      (node (ref "IC6") (pin "N3") (pinfunction "PA0_N3") (pintype "bidirectional"))
      (node (ref "R19") (pin "2") (pinfunction "2_2") (pintype "passive"))
    )
    (net (code "155") (name "/VBATT_SENS") (class "Default")
      (node (ref "IC6") (pin "R2") (pinfunction "PA3_R2") (pintype "bidirectional"))
    )
    (net (code "156") (name "/WiFi_CTS") (class "Default")
      (node (ref "IC6") (pin "C15") (pinfunction "PA11_C15") (pintype "bidirectional"))
    )
    (net (code "157") (name "/WiFi_IRQ") (class "Default")
      (node (ref "IC6") (pin "D9") (pinfunction "PG9_D9") (pintype "bidirectional"))
    )
    (net (code "158") (name "/WiFi_MISO") (class "Default")
      (node (ref "IC6") (pin "C14") (pinfunction "PI2_C14") (pintype "bidirectional"))
    )
    (net (code "159") (name "/WiFi_MOSI") (class "Default")
      (node (ref "IC6") (pin "C13") (pinfunction "PI3_C13") (pintype "bidirectional"))
    )
    (net (code "160") (name "/WiFi_PWE") (class "Default")
      (node (ref "IC6") (pin "A13") (pinfunction "PA15_A13") (pintype "bidirectional"))
    )
    (net (code "161") (name "/WiFi_RTS") (class "Default")
      (node (ref "IC6") (pin "B15") (pinfunction "PA12_B15") (pintype "bidirectional"))
    )
    (net (code "162") (name "/WiFi_RX") (class "Default")
      (node (ref "IC6") (pin "D15") (pinfunction "PA10_D15") (pintype "bidirectional"))
    )
    (net (code "163") (name "/WiFi_SCL") (class "Default")
      (node (ref "IC6") (pin "C11") (pinfunction "PD3_C11") (pintype "bidirectional"))
    )
    (net (code "164") (name "/WiFi_TX") (class "Default")
      (node (ref "IC6") (pin "E15") (pinfunction "PA9_E15") (pintype "bidirectional"))
    )
    (net (code "165") (name "/uSD_CLK") (class "Default")
      (node (ref "IC6") (pin "A12") (pinfunction "PC12_A12") (pintype "bidirectional"))
    )
    (net (code "166") (name "/uSD_CMD") (class "Default")
      (node (ref "IC6") (pin "D12") (pinfunction "PD2_D12") (pintype "bidirectional"))
    )
    (net (code "167") (name "/uSD_D0") (class "Default")
      (node (ref "IC6") (pin "G14") (pinfunction "PC8_G14") (pintype "bidirectional"))
    )
    (net (code "168") (name "/uSD_D1") (class "Default")
      (node (ref "IC6") (pin "F14") (pinfunction "PC9_F14") (pintype "bidirectional"))
    )
    (net (code "169") (name "/uSD_D2") (class "Default")
      (node (ref "IC6") (pin "B14") (pinfunction "PC10_B14") (pintype "bidirectional"))
    )
    (net (code "170") (name "/uSD_D3") (class "Default")
      (node (ref "IC6") (pin "B13") (pinfunction "PC11_B13") (pintype "bidirectional"))
    )
    (net (code "171") (name "/uSD_Detect") (class "Default")
      (node (ref "IC6") (pin "N13") (pinfunction "PH7_N13") (pintype "bidirectional"))
    )
    (net (code "172") (name "/~{NRST}") (class "Default")
      (node (ref "BT1") (pin "1") (pinfunction "1_1") (pintype "passive"))
      (node (ref "C25") (pin "2") (pinfunction "2_2") (pintype "passive"))
      (node (ref "IC6") (pin "J1") (pinfunction "NRST_J1") (pintype "bidirectional"))
      (node (ref "R15") (pin "2") (pinfunction "2_2") (pintype "passive"))
    )
    (net (code "173") (name "3v3") (class "Default")
      (node (ref "BT2") (pin "1") (pinfunction "1_1") (pintype "passive"))
      (node (ref "C29") (pin "2") (pinfunction "2_2") (pintype "passive"))
      (node (ref "R15") (pin "1") (pinfunction "1_1") (pintype "passive"))
      (node (ref "R22") (pin "1") (pinfunction "1_1") (pintype "passive"))
      (node (ref "R23") (pin "2") (pinfunction "2_2") (pintype "passive"))
      (node (ref "Y2") (pin "4") (pinfunction "VDD_4") (pintype "passive"))
    )
    (net (code "174") (name "GND") (class "Default")
      (node (ref "BT1") (pin "2") (pinfunction "2_2") (pintype "passive"))
      (node (ref "C25") (pin "1") (pinfunction "1_1") (pintype "passive"))
      (node (ref "C26") (pin "1") (pinfunction "1_1") (pintype "passive"))
      (node (ref "C27") (pin "1") (pinfunction "1_1") (pintype "passive"))
      (node (ref "C28") (pin "1") (pinfunction "1_1") (pintype "passive"))
      (node (ref "C29") (pin "1") (pinfunction "1_1") (pintype "passive"))
      (node (ref "C30") (pin "1") (pinfunction "1_1") (pintype "passive"))
      (node (ref "C31") (pin "1") (pinfunction "1_1") (pintype "passive"))
      (node (ref "C32") (pin "1") (pinfunction "1_1") (pintype "passive"))
      (node (ref "C33") (pin "1") (pinfunction "1_1") (pintype "passive"))
      (node (ref "C34") (pin "1") (pinfunction "1_1") (pintype "passive"))
      (node (ref "C35") (pin "1") (pinfunction "1_1") (pintype "passive"))
      (node (ref "C36") (pin "1") (pinfunction "1_1") (pintype "passive"))
      (node (ref "C37") (pin "1") (pinfunction "1_1") (pintype "passive"))
      (node (ref "C38") (pin "1") (pinfunction "1_1") (pintype "passive"))
      (node (ref "C39") (pin "1") (pinfunction "1_1") (pintype "passive"))
      (node (ref "C40") (pin "1") (pinfunction "1_1") (pintype "passive"))
      (node (ref "C41") (pin "1") (pinfunction "1_1") (pintype "passive"))
      (node (ref "C42") (pin "1") (pinfunction "1_1") (pintype "passive"))
      (node (ref "C43") (pin "1") (pinfunction "1_1") (pintype "passive"))
      (node (ref "C44") (pin "1") (pinfunction "1_1") (pintype "passive"))
      (node (ref "C45") (pin "1") (pinfunction "1_1") (pintype "passive"))
      (node (ref "C46") (pin "1") (pinfunction "1_1") (pintype "passive"))
      (node (ref "C47") (pin "1") (pinfunction "1_1") (pintype "passive"))
      (node (ref "C48") (pin "1") (pinfunction "1_1") (pintype "passive"))
      (node (ref "C49") (pin "1") (pinfunction "1_1") (pintype "passive"))
      (node (ref "C50") (pin "1") (pinfunction "1_1") (pintype "passive"))
      (node (ref "C51") (pin "1") (pinfunction "1_1") (pintype "passive"))
      (node (ref "C52") (pin "1") (pinfunction "1_1") (pintype "passive"))
      (node (ref "C53") (pin "1") (pinfunction "1_1") (pintype "passive"))
      (node (ref "C54") (pin "1") (pinfunction "1_1") (pintype "passive"))
      (node (ref "C55") (pin "1") (pinfunction "1_1") (pintype "passive"))
      (node (ref "IC6") (pin "F10") (pinfunction "VSS_F10") (pintype "power_in"))
      (node (ref "IC6") (pin "F2") (pinfunction "VSS_F2") (pintype "power_in"))
      (node (ref "IC6") (pin "F6") (pinfunction "VSS_F6") (pintype "power_in"))
      (node (ref "IC6") (pin "F7") (pinfunction "VSS_F7") (pintype "power_in"))
      (node (ref "IC6") (pin "F8") (pinfunction "VSS_F8") (pintype "power_in"))
      (node (ref "IC6") (pin "F9") (pinfunction "VSS_F9") (pintype "power_in"))
      (node (ref "IC6") (pin "G10") (pinfunction "VSS_G10") (pintype "power_in"))
      (node (ref "IC6") (pin "G6") (pinfunction "VSS_G6") (pintype "power_in"))
      (node (ref "IC6") (pin "H10") (pinfunction "VSS_H10") (pintype "power_in"))
      (node (ref "IC6") (pin "H6") (pinfunction "VSS_H6") (pintype "power_in"))
      (node (ref "IC6") (pin "J10") (pinfunction "VSS_J10") (pintype "power_in"))
      (node (ref "IC6") (pin "J6") (pinfunction "VSS_J6") (pintype "power_in"))
      (node (ref "IC6") (pin "K10") (pinfunction "VSS_K10") (pintype "power_in"))
      (node (ref "IC6") (pin "K6") (pinfunction "VSS_K6") (pintype "power_in"))
      (node (ref "IC6") (pin "K7") (pinfunction "VSS_K7") (pintype "power_in"))
      (node (ref "IC6") (pin "K8") (pinfunction "VSS_K8") (pintype "power_in"))
      (node (ref "IC6") (pin "K9") (pinfunction "VSS_K9") (pintype "power_in"))
      (node (ref "IC6") (pin "L6") (pinfunction "VSS_L6") (pintype "power_in"))
      (node (ref "IC6") (pin "M1") (pinfunction "VSSA_M1") (pintype "power_in"))
      (node (ref "IC6") (pin "N1") (pinfunction "VREF-_N1") (pintype "power_in"))
      (node (ref "R16") (pin "1") (pinfunction "1_1") (pintype "passive"))
      (node (ref "R18") (pin "1") (pinfunction "1_1") (pintype "passive"))
      (node (ref "R21") (pin "1") (pinfunction "1_1") (pintype "passive"))
      (node (ref "Y2") (pin "2") (pinfunction "GND_2") (pintype "passive"))
    )
    (net (code "175") (name "Net-(BT2-Pad2)") (class "Default")
      (node (ref "BT2") (pin "2") (pinfunction "2_2") (pintype "passive"))
      (node (ref "R19") (pin "1") (pinfunction "1_1") (pintype "passive"))
      (node (ref "R21") (pin "2") (pinfunction "2_2") (pintype "passive"))
    )
    (net (code "176") (name "Net-(IC6A-PC14)") (class "Default")
      (node (ref "C27") (pin "2") (pinfunction "2_2") (pintype "passive"))
      (node (ref "IC6") (pin "E1") (pinfunction "PC14_E1") (pintype "bidirectional"))
      (node (ref "Y1") (pin "2") (pinfunction "2_2") (pintype "passive"))
    )
    (net (code "177") (name "Net-(IC6A-PC15)") (class "Default")
      (node (ref "C28") (pin "2") (pinfunction "2_2") (pintype "passive"))
      (node (ref "IC6") (pin "F1") (pinfunction "PC15_F1") (pintype "bidirectional"))
      (node (ref "Y1") (pin "1") (pinfunction "1_1") (pintype "passive"))
    )
    (net (code "178") (name "Net-(IC6B-PH0)") (class "Default")
      (node (ref "IC6") (pin "G1") (pinfunction "PH0_G1") (pintype "bidirectional"))
      (node (ref "R20") (pin "1") (pinfunction "1_1") (pintype "passive"))
    )
    (net (code "179") (name "Net-(IC6C-BOOT0)") (class "Default")
      (node (ref "IC6") (pin "E6") (pinfunction "BOOT0_E6") (pintype "input"))
      (node (ref "R16") (pin "2") (pinfunction "2_2") (pintype "passive"))
    )
    (net (code "180") (name "Net-(IC6C-BYPASS_REG)") (class "Default")
      (node (ref "IC6") (pin "L5") (pinfunction "BYPASS_REG_L5") (pintype "input"))
      (node (ref "R18") (pin "2") (pinfunction "2_2") (pintype "passive"))
    )
    (net (code "181") (name "Net-(IC6C-PDR_ON)") (class "Default")
      (node (ref "IC6") (pin "E5") (pinfunction "PDR_ON_E5") (pintype "passive"))
      (node (ref "R17") (pin "2") (pinfunction "2_2") (pintype "passive"))
    )
    (net (code "182") (name "Net-(IC6D-VCAP_1)") (class "Default")
      (node (ref "C32") (pin "2") (pinfunction "2_2") (pintype "passive"))
      (node (ref "IC6") (pin "L11") (pinfunction "VCAP_1_L11") (pintype "power_in"))
    )
    (net (code "183") (name "Net-(IC6D-VCAP_2)") (class "Default")
      (node (ref "C33") (pin "2") (pinfunction "2_2") (pintype "passive"))
      (node (ref "IC6") (pin "E11") (pinfunction "VCAP_2_E11") (pintype "power_in"))
    )
    (net (code "184") (name "Net-(Y2-TRI)") (class "Default")
      (node (ref "R22") (pin "2") (pinfunction "2_2") (pintype "passive"))
      (node (ref "Y2") (pin "1") (pinfunction "TRI_1") (pintype "passive"))
    )
    (net (code "185") (name "VDD") (class "Default")
      (node (ref "C34") (pin "2") (pinfunction "2_2") (pintype "passive"))
      (node (ref "C35") (pin "2") (pinfunction "2_2") (pintype "passive"))
      (node (ref "C36") (pin "2") (pinfunction "2_2") (pintype "passive"))
      (node (ref "C37") (pin "2") (pinfunction "2_2") (pintype "passive"))
      (node (ref "C38") (pin "2") (pinfunction "2_2") (pintype "passive"))
      (node (ref "C39") (pin "2") (pinfunction "2_2") (pintype "passive"))
      (node (ref "C40") (pin "2") (pinfunction "2_2") (pintype "passive"))
      (node (ref "C41") (pin "2") (pinfunction "2_2") (pintype "passive"))
      (node (ref "C42") (pin "2") (pinfunction "2_2") (pintype "passive"))
      (node (ref "C43") (pin "2") (pinfunction "2_2") (pintype "passive"))
      (node (ref "C44") (pin "2") (pinfunction "2_2") (pintype "passive"))
      (node (ref "C47") (pin "2") (pinfunction "2_2") (pintype "passive"))
      (node (ref "C48") (pin "2") (pinfunction "2_2") (pintype "passive"))
      (node (ref "C49") (pin "2") (pinfunction "2_2") (pintype "passive"))
      (node (ref "C50") (pin "2") (pinfunction "2_2") (pintype "passive"))
      (node (ref "C51") (pin "2") (pinfunction "2_2") (pintype "passive"))
      (node (ref "C52") (pin "2") (pinfunction "2_2") (pintype "passive"))
      (node (ref "C53") (pin "2") (pinfunction "2_2") (pintype "passive"))
      (node (ref "C54") (pin "2") (pinfunction "2_2") (pintype "passive"))
      (node (ref "C55") (pin "2") (pinfunction "2_2") (pintype "passive"))
      (node (ref "FB1") (pin "2") (pinfunction "2_2") (pintype "passive"))
      (node (ref "IC6") (pin "E10") (pinfunction "VDD_E10") (pintype "power_in"))
      (node (ref "IC6") (pin "E7") (pinfunction "VDD_E7") (pintype "power_in"))
      (node (ref "IC6") (pin "E8") (pinfunction "VDD_E8") (pintype "power_in"))
      (node (ref "IC6") (pin "E9") (pinfunction "VDD_E9") (pintype "power_in"))
      (node (ref "IC6") (pin "F11") (pinfunction "VDD_F11") (pintype "power_in"))
      (node (ref "IC6") (pin "F4") (pinfunction "VDD_F4") (pintype "power_in"))
      (node (ref "IC6") (pin "F5") (pinfunction "VDD_F5") (pintype "power_in"))
      (node (ref "IC6") (pin "G11") (pinfunction "VDDUSB_G11") (pintype "power_in"))
      (node (ref "IC6") (pin "G5") (pinfunction "VDD_G5") (pintype "power_in"))
      (node (ref "IC6") (pin "H11") (pinfunction "VDD_H11") (pintype "power_in"))
      (node (ref "IC6") (pin "H5") (pinfunction "VDD_H5") (pintype "power_in"))
      (node (ref "IC6") (pin "J11") (pinfunction "VDD_J11") (pintype "power_in"))
      (node (ref "IC6") (pin "J5") (pinfunction "VDD_J5") (pintype "power_in"))
      (node (ref "IC6") (pin "K11") (pinfunction "VDD_K11") (pintype "power_in"))
      (node (ref "IC6") (pin "K5") (pinfunction "VDD_K5") (pintype "power_in"))
      (node (ref "IC6") (pin "L10") (pinfunction "VDD_L10") (pintype "power_in"))
      (node (ref "IC6") (pin "L7") (pinfunction "VDD_L7") (pintype "power_in"))
      (node (ref "IC6") (pin "L8") (pinfunction "VDD_L8") (pintype "power_in"))
      (node (ref "IC6") (pin "L9") (pinfunction "VDD_L9") (pintype "power_in"))
      (node (ref "R17") (pin "1") (pinfunction "1_1") (pintype "passive"))
      (node (ref "R23") (pin "1") (pinfunction "1_1") (pintype "passive"))
    )
    (net (code "186") (name "VDDA") (class "Default")
      (node (ref "C45") (pin "2") (pinfunction "2_2") (pintype "passive"))
      (node (ref "C46") (pin "2") (pinfunction "2_2") (pintype "passive"))
      (node (ref "FB1") (pin "1") (pinfunction "1_1") (pintype "passive"))
      (node (ref "IC6") (pin "C1") (pinfunction "VBAT_C1") (pintype "power_in"))
      (node (ref "IC6") (pin "R1") (pinfunction "VDDA_R1") (pintype "power_in"))
      (node (ref "R24") (pin "2") (pinfunction "2_2") (pintype "passive"))
    )
    (net (code "187") (name "VREF+") (class "Default")
      (node (ref "C30") (pin "2") (pinfunction "2_2") (pintype "passive"))
      (node (ref "C31") (pin "2") (pinfunction "2_2") (pintype "passive"))
      (node (ref "IC6") (pin "P1") (pinfunction "VREF+_P1") (pintype "power_in"))
      (node (ref "R24") (pin "1") (pinfunction "1_1") (pintype "passive"))
    )
    (net (code "188") (name "unconnected-(IC6B-PH1-PadH1)") (class "Default")
      (node (ref "IC6") (pin "H1") (pinfunction "PH1_H1") (pintype "bidirectional+no_connect"))
    )
  )
)
